# E-Card.net
KiCad netlist of a schematic drawn in Altium Designer
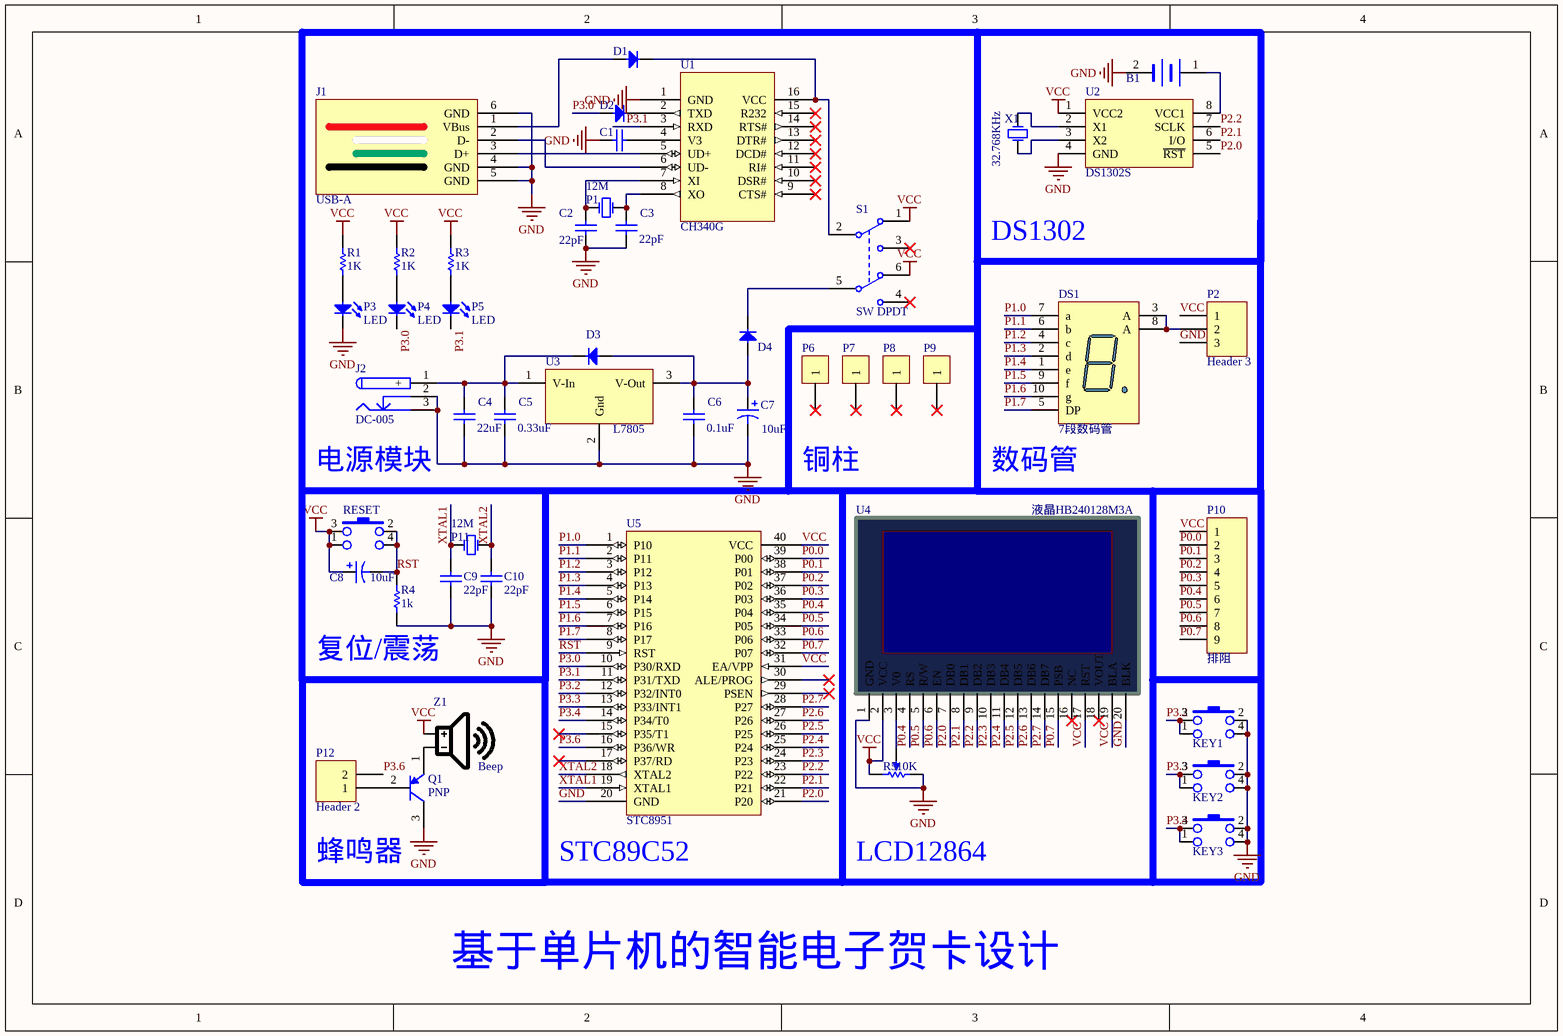
[diagram p0: E-Card.SchDoc]

(export (version "E")
  (design (tool "Eeschema 10.0.6"))
  (components
    (comp (ref "B1") (value "CR1220") (footprint "BATTERY") (libsource (lib "E-Card") (part "BATTERY")))
    (comp (ref "C1")
      (value "0.1uF")
      (footprint "Cap")
      (description "普通电容")
      (libsource (lib "E-Card") (part "Cap"))
    )
    (comp (ref "C2")
      (value "22pF")
      (footprint "Cap")
      (description "普通电容")
      (libsource (lib "E-Card") (part "Cap"))
    )
    (comp (ref "C3")
      (value "22pF")
      (footprint "Cap")
      (description "普通电容")
      (libsource (lib "E-Card") (part "Cap"))
    )
    (comp (ref "C4")
      (value "22uF")
      (footprint "Cap")
      (description "普通电容")
      (libsource (lib "E-Card") (part "Cap"))
    )
    (comp (ref "C5")
      (value "0.33uF")
      (footprint "Cap")
      (description "普通电容")
      (libsource (lib "E-Card") (part "Cap"))
    )
    (comp (ref "C6")
      (value "0.1uF")
      (footprint "Cap")
      (description "普通电容")
      (libsource (lib "E-Card") (part "Cap"))
    )
    (comp (ref "C7")
      (value "10uF")
      (footprint "电解电容")
      (description "电解电容")
      (libsource (lib "E-Card") (part "电解电容"))
    )
    (comp (ref "C8")
      (value "10uF")
      (footprint "电解电容")
      (description "电解电容")
      (libsource (lib "E-Card") (part "电解电容"))
    )
    (comp (ref "C9")
      (value "22pF")
      (footprint "Cap")
      (description "普通电容")
      (libsource (lib "E-Card") (part "Cap"))
    )
    (comp (ref "C10")
      (value "22pF")
      (footprint "Cap")
      (description "普通电容")
      (libsource (lib "E-Card") (part "Cap"))
    )
    (comp (ref "D1")
      (value "Diode")
      (footprint "Diode")
      (description "二极管")
      (fields (field (name "PUBLISHER") "Altium Limited"))
      (libsource (lib "E-Card") (part "Diode"))
    )
    (comp (ref "D2")
      (value "1N4007")
      (footprint "Diode")
      (description "二极管Diode")
      (fields (field (name "PUBLISHER") "Altium Limited"))
      (libsource (lib "E-Card") (part "Diode"))
    )
    (comp (ref "D3")
      (value "Diode")
      (footprint "Diode")
      (description "二极管")
      (fields (field (name "PUBLISHER") "Altium Limited"))
      (libsource (lib "E-Card") (part "Diode"))
    )
    (comp (ref "D4")
      (value "Diode")
      (footprint "Diode")
      (description "二极管")
      (fields (field (name "PUBLISHER") "Altium Limited"))
      (libsource (lib "E-Card") (part "Diode"))
    )
    (comp (ref "DS1")
      (value "7-Segment")
      (footprint "7-Segment")
      (description "14.2 mm General Purpose Blue 7-Segment Display: CA, RH DP, Gray Surface")
      (fields (field (name "ALTIUM_UNNAMED_1") "7段数码管") (field (name "PUBLISHER") "Altium Limited"))
      (libsource (lib "E-Card") (part "7-Segment"))
    )
    (comp (ref "J1") (value "USB-A") (footprint "USB-A") (libsource (lib "E-Card") (part "USB-A")))
    (comp (ref "J2")
      (value "DC-005")
      (footprint "DC JACK")
      (description "DC 电源座")
      (fields (field (name "MANUFACTURER") "Kycon"))
      (libsource (lib "E-Card") (part "DC JACK"))
    )
    (comp (ref "KEY1") (value "SW-66B7") (footprint "SW-66") (libsource (lib "E-Card") (part "SW-66B7")))
    (comp (ref "KEY2") (value "SW-66B7") (footprint "SW-66") (libsource (lib "E-Card") (part "SW-66B7")))
    (comp (ref "KEY3") (value "SW-66B7") (footprint "SW-66") (libsource (lib "E-Card") (part "SW-66B7")))
    (comp (ref "P1")
      (value "12M")
      (footprint "XTAL 12M")
      (description "12MHZ振荡器 【2PIN】")
      (libsource (lib "E-Card") (part "XTAL 12M"))
    )
    (comp (ref "P2")
      (value "Header 3")
      (footprint "Header 3")
      (description "Header, 3-Pin")
      (fields (field (name "PUBLISHER") "Altium Limited"))
      (libsource (lib "E-Card") (part "Header 3"))
    )
    (comp (ref "P3")
      (value "LED")
      (footprint "LED")
      (description "LED灯")
      (libsource (lib "E-Card") (part "LED"))
    )
    (comp (ref "P4")
      (value "LED")
      (footprint "LED")
      (description "LED灯")
      (libsource (lib "E-Card") (part "LED"))
    )
    (comp (ref "P5")
      (value "LED")
      (footprint "LED")
      (description "LED灯")
      (libsource (lib "E-Card") (part "LED"))
    )
    (comp (ref "P6")
      (value "CU-M3X6-10")
      (footprint "CU-M3X6-10")
      (description "10mm长M3六角铜柱")
      (fields (field (name "PUBLISHER") "Altium Limited"))
      (libsource (lib "E-Card") (part "CU-M3X6-10"))
    )
    (comp (ref "P7")
      (value "CU-M3X6-10")
      (footprint "CU-M3X6-10")
      (description "10mm长M3六角铜柱")
      (fields (field (name "PUBLISHER") "Altium Limited"))
      (libsource (lib "E-Card") (part "CU-M3X6-10"))
    )
    (comp (ref "P8")
      (value "CU-M3X6-10")
      (footprint "CU-M3X6-10")
      (description "10mm长M3六角铜柱")
      (fields (field (name "PUBLISHER") "Altium Limited"))
      (libsource (lib "E-Card") (part "CU-M3X6-10"))
    )
    (comp (ref "P9")
      (value "CU-M3X6-10")
      (footprint "CU-M3X6-10")
      (description "10mm长M3六角铜柱")
      (fields (field (name "PUBLISHER") "Altium Limited"))
      (libsource (lib "E-Card") (part "CU-M3X6-10"))
    )
    (comp (ref "P10")
      (value "排阻")
      (footprint "排阻")
      (description "Header, 9-Pin")
      (fields (field (name "PUBLISHER") "Altium Limited"))
      (libsource (lib "E-Card") (part "排阻"))
    )
    (comp (ref "P11")
      (value "12M")
      (footprint "XTAL 12M")
      (description "12MHZ振荡器 【2PIN】")
      (libsource (lib "E-Card") (part "XTAL 12M"))
    )
    (comp (ref "P12")
      (value "Header 2")
      (footprint "Header 2")
      (description "针座/孔座 180度")
      (fields (field (name "PUBLISHER") "Altium Limited"))
      (libsource (lib "E-Card") (part "Header 2"))
    )
    (comp (ref "Q1")
      (value "PNP")
      (footprint "PNP")
      (description "PNP Bipolar Transistor")
      (fields (field (name "PUBLISHER") "Altium Limited"))
      (libsource (lib "E-Card") (part "PNP"))
    )
    (comp (ref "R1")
      (value "1K")
      (footprint "RES")
      (description "电阻")
      (libsource (lib "E-Card") (part "RES"))
    )
    (comp (ref "R2")
      (value "1K")
      (footprint "RES")
      (description "电阻")
      (libsource (lib "E-Card") (part "RES"))
    )
    (comp (ref "R3")
      (value "1K")
      (footprint "RES")
      (description "电阻")
      (libsource (lib "E-Card") (part "RES"))
    )
    (comp (ref "R4")
      (value "1k")
      (footprint "RES")
      (description "电阻")
      (libsource (lib "E-Card") (part "RES"))
    )
    (comp (ref "R5")
      (value "10K")
      (footprint "RPot")
      (description "可调 电阻")
      (fields (field (name "Comment") "RPot") (field (name "PUBLISHER") "Altium Limited"))
      (libsource (lib "E-Card") (part "RPot"))
    )
    (comp (ref "RESET") (value "SW-66B7") (footprint "SW-66") (libsource (lib "E-Card") (part "SW-66B7")))
    (comp (ref "S1")
      (value "SW DPDT")
      (footprint "SW DPDT")
      (description "自锁开关 （双刀双掷）")
      (fields (field (name "PUBLISHER") "Altium Limited"))
      (libsource (lib "E-Card") (part "SW DPDT"))
    )
    (comp (ref "U1")
      (value "CH340G")
      (footprint "CH340G")
      (description "USB to TTL Serial / UART")
      (libsource (lib "E-Card") (part "CH340G"))
    )
    (comp (ref "U2")
      (value "DS1302S")
      (footprint "DS1302")
      (description "时钟芯片 SOP127P780-8")
      (libsource (lib "E-Card") (part "DS1302"))
    )
    (comp (ref "U3")
      (value "L7805")
      (footprint "L7805")
      (description "1.5A Vin:40V(max) Vout:5-24V -55 ~ 150°C LDO稳压器")
      (libsource (lib "E-Card") (part "L7805"))
    )
    (comp (ref "U4")
      (value "液晶HB240128M3A")
      (footprint "LCD12864")
      (libsource (lib "E-Card") (part "液晶HB240128M3A"))
    )
    (comp (ref "U5")
      (value "STC8951")
      (footprint "STC8951")
      (description "51单片机")
      (libsource (lib "E-Card") (part "STC8951"))
    )
    (comp (ref "X1")
      (value "32.768KHz")
      (footprint "XTAL 32768")
      (description "32768HZ振荡器 【2PIN】")
      (libsource (lib "E-Card") (part "XTAL 32768"))
    )
    (comp (ref "Z1")
      (value "Beep")
      (footprint "Beep")
      (description "蜂鸣器")
      (libsource (lib "E-Card") (part "Beep"))
    )
  )
  (nets
    (net (code "1") (name "/P0.0") (class "Default")
      (node (ref "P10") (pin "2") (pinfunction "2_2") (pintype "passive"))
      (node (ref "U5") (pin "39") (pinfunction "P00_39") (pintype "bidirectional"))
    )
    (net (code "2") (name "/P0.1") (class "Default")
      (node (ref "P10") (pin "3") (pinfunction "3_3") (pintype "passive"))
      (node (ref "U5") (pin "38") (pinfunction "P01_38") (pintype "bidirectional"))
    )
    (net (code "3") (name "/P0.2") (class "Default")
      (node (ref "P10") (pin "4") (pinfunction "4_4") (pintype "passive"))
      (node (ref "U5") (pin "37") (pinfunction "P02_37") (pintype "bidirectional"))
    )
    (net (code "4") (name "/P0.3") (class "Default")
      (node (ref "P10") (pin "5") (pinfunction "5_5") (pintype "passive"))
      (node (ref "U5") (pin "36") (pinfunction "P03_36") (pintype "bidirectional"))
    )
    (net (code "5") (name "/P0.4") (class "Default")
      (node (ref "P10") (pin "6") (pinfunction "6_6") (pintype "passive"))
      (node (ref "U4") (pin "4") (pinfunction "RS_4") (pintype "passive"))
      (node (ref "U5") (pin "35") (pinfunction "P04_35") (pintype "bidirectional"))
    )
    (net (code "6") (name "/P0.5") (class "Default")
      (node (ref "P10") (pin "7") (pinfunction "7_7") (pintype "passive"))
      (node (ref "U4") (pin "5") (pinfunction "R/W_5") (pintype "passive"))
      (node (ref "U5") (pin "34") (pinfunction "P05_34") (pintype "bidirectional"))
    )
    (net (code "7") (name "/P0.6") (class "Default")
      (node (ref "P10") (pin "8") (pinfunction "8_8") (pintype "passive"))
      (node (ref "U4") (pin "6") (pinfunction "EN_6") (pintype "passive"))
      (node (ref "U5") (pin "33") (pinfunction "P06_33") (pintype "bidirectional"))
    )
    (net (code "8") (name "/P0.7") (class "Default")
      (node (ref "P10") (pin "9") (pinfunction "9_9") (pintype "passive"))
      (node (ref "U4") (pin "15") (pinfunction "PSB_15") (pintype "passive"))
      (node (ref "U5") (pin "32") (pinfunction "P07_32") (pintype "bidirectional"))
    )
    (net (code "9") (name "/P1.0") (class "Default")
      (node (ref "DS1") (pin "7") (pinfunction "a_7") (pintype "passive"))
      (node (ref "U5") (pin "1") (pinfunction "P10_1") (pintype "bidirectional"))
    )
    (net (code "10") (name "/P1.1") (class "Default")
      (node (ref "DS1") (pin "6") (pinfunction "b_6") (pintype "passive"))
      (node (ref "U5") (pin "2") (pinfunction "P11_2") (pintype "bidirectional"))
    )
    (net (code "11") (name "/P1.2") (class "Default")
      (node (ref "DS1") (pin "4") (pinfunction "c_4") (pintype "passive"))
      (node (ref "U5") (pin "3") (pinfunction "P12_3") (pintype "bidirectional"))
    )
    (net (code "12") (name "/P1.3") (class "Default")
      (node (ref "DS1") (pin "2") (pinfunction "d_2") (pintype "passive"))
      (node (ref "U5") (pin "4") (pinfunction "P13_4") (pintype "bidirectional"))
    )
    (net (code "13") (name "/P1.4") (class "Default")
      (node (ref "DS1") (pin "1") (pinfunction "e_1") (pintype "passive"))
      (node (ref "U5") (pin "5") (pinfunction "P14_5") (pintype "bidirectional"))
    )
    (net (code "14") (name "/P1.5") (class "Default")
      (node (ref "DS1") (pin "9") (pinfunction "f_9") (pintype "passive"))
      (node (ref "U5") (pin "6") (pinfunction "P15_6") (pintype "bidirectional"))
    )
    (net (code "15") (name "/P1.6") (class "Default")
      (node (ref "DS1") (pin "10") (pinfunction "g_10") (pintype "passive"))
      (node (ref "U5") (pin "7") (pinfunction "P16_7") (pintype "bidirectional"))
    )
    (net (code "16") (name "/P1.7") (class "Default")
      (node (ref "DS1") (pin "5") (pinfunction "DP_5") (pintype "passive"))
      (node (ref "U5") (pin "8") (pinfunction "P17_8") (pintype "bidirectional"))
    )
    (net (code "17") (name "/P2.0") (class "Default")
      (node (ref "U2") (pin "5") (pinfunction "~{RST}_5") (pintype "passive"))
      (node (ref "U4") (pin "7") (pinfunction "DB0_7") (pintype "passive"))
      (node (ref "U5") (pin "21") (pinfunction "P20_21") (pintype "bidirectional"))
    )
    (net (code "18") (name "/P2.1") (class "Default")
      (node (ref "U2") (pin "6") (pinfunction "I/O_6") (pintype "passive"))
      (node (ref "U4") (pin "8") (pinfunction "DB1_8") (pintype "passive"))
      (node (ref "U5") (pin "22") (pinfunction "P21_22") (pintype "bidirectional"))
    )
    (net (code "19") (name "/P2.2") (class "Default")
      (node (ref "U2") (pin "7") (pinfunction "SCLK_7") (pintype "passive"))
      (node (ref "U4") (pin "9") (pinfunction "DB2_9") (pintype "passive"))
      (node (ref "U5") (pin "23") (pinfunction "P22_23") (pintype "bidirectional"))
    )
    (net (code "20") (name "/P2.3") (class "Default")
      (node (ref "U4") (pin "10") (pinfunction "DB3_10") (pintype "passive"))
      (node (ref "U5") (pin "24") (pinfunction "P23_24") (pintype "bidirectional"))
    )
    (net (code "21") (name "/P2.4") (class "Default")
      (node (ref "U4") (pin "11") (pinfunction "DB4_11") (pintype "passive"))
      (node (ref "U5") (pin "25") (pinfunction "P24_25") (pintype "bidirectional"))
    )
    (net (code "22") (name "/P2.5") (class "Default")
      (node (ref "U4") (pin "12") (pinfunction "DB5_12") (pintype "passive"))
      (node (ref "U5") (pin "26") (pinfunction "P25_26") (pintype "bidirectional"))
    )
    (net (code "23") (name "/P2.6") (class "Default")
      (node (ref "U4") (pin "13") (pinfunction "DB6_13") (pintype "passive"))
      (node (ref "U5") (pin "27") (pinfunction "P26_27") (pintype "bidirectional"))
    )
    (net (code "24") (name "/P2.7") (class "Default")
      (node (ref "U4") (pin "14") (pinfunction "DB7_14") (pintype "passive"))
      (node (ref "U5") (pin "28") (pinfunction "P27_28") (pintype "bidirectional"))
    )
    (net (code "25") (name "/P3.0") (class "Default")
      (node (ref "D2") (pin "1") (pinfunction "A_1") (pintype "passive"))
      (node (ref "P4") (pin "2") (pinfunction "K_2") (pintype "passive"))
      (node (ref "U5") (pin "10") (pinfunction "P30/RXD_10") (pintype "bidirectional"))
    )
    (net (code "26") (name "/P3.1") (class "Default")
      (node (ref "P5") (pin "2") (pinfunction "K_2") (pintype "passive"))
      (node (ref "U1") (pin "3") (pinfunction "RXD_3") (pintype "input"))
      (node (ref "U5") (pin "11") (pinfunction "P31/TXD_11") (pintype "bidirectional"))
    )
    (net (code "27") (name "/P3.2") (class "Default")
      (node (ref "KEY1") (pin "1") (pinfunction "1_1") (pintype "passive"))
      (node (ref "KEY1") (pin "3") (pinfunction "3_3") (pintype "passive"))
      (node (ref "U5") (pin "12") (pinfunction "P32/INT0_12") (pintype "bidirectional"))
    )
    (net (code "28") (name "/P3.3") (class "Default")
      (node (ref "KEY2") (pin "1") (pinfunction "1_1") (pintype "passive"))
      (node (ref "KEY2") (pin "3") (pinfunction "3_3") (pintype "passive"))
      (node (ref "U5") (pin "13") (pinfunction "P33/INT1_13") (pintype "bidirectional"))
    )
    (net (code "29") (name "/P3.4") (class "Default")
      (node (ref "KEY3") (pin "1") (pinfunction "1_1") (pintype "passive"))
      (node (ref "KEY3") (pin "3") (pinfunction "3_3") (pintype "passive"))
      (node (ref "U5") (pin "14") (pinfunction "P34/T0_14") (pintype "bidirectional"))
    )
    (net (code "30") (name "/P3.6") (class "Default")
      (node (ref "P12") (pin "2") (pinfunction "2_2") (pintype "passive"))
      (node (ref "U5") (pin "16") (pinfunction "P36/WR_16") (pintype "bidirectional"))
    )
    (net (code "31") (name "/RST") (class "Default")
      (node (ref "C8") (pin "2") (pinfunction "2_2") (pintype "passive"))
      (node (ref "R4") (pin "2") (pinfunction "2_2") (pintype "passive"))
      (node (ref "RESET") (pin "2") (pinfunction "2_2") (pintype "passive"))
      (node (ref "RESET") (pin "4") (pinfunction "4_4") (pintype "passive"))
      (node (ref "U5") (pin "9") (pinfunction "RST_9") (pintype "input"))
    )
    (net (code "32") (name "/XTAL1") (class "Default")
      (node (ref "C9") (pin "2") (pinfunction "2_2") (pintype "passive"))
      (node (ref "P11") (pin "1") (pinfunction "OSC1_1") (pintype "passive"))
      (node (ref "U5") (pin "19") (pinfunction "XTAL1_19") (pintype "input"))
    )
    (net (code "33") (name "/XTAL2") (class "Default")
      (node (ref "C10") (pin "2") (pinfunction "2_2") (pintype "passive"))
      (node (ref "P11") (pin "2") (pinfunction "OSC2_2") (pintype "passive"))
      (node (ref "U5") (pin "18") (pinfunction "XTAL2_18") (pintype "output"))
    )
    (net (code "34") (name "GND") (class "Default")
      (node (ref "B1") (pin "2") (pinfunction "-_2") (pintype "passive"))
      (node (ref "C1") (pin "1") (pinfunction "1_1") (pintype "passive"))
      (node (ref "C10") (pin "1") (pinfunction "1_1") (pintype "passive"))
      (node (ref "C2") (pin "2") (pinfunction "2_2") (pintype "passive"))
      (node (ref "C3") (pin "2") (pinfunction "2_2") (pintype "passive"))
      (node (ref "C4") (pin "2") (pinfunction "2_2") (pintype "passive"))
      (node (ref "C5") (pin "2") (pinfunction "2_2") (pintype "passive"))
      (node (ref "C6") (pin "1") (pinfunction "1_1") (pintype "passive"))
      (node (ref "C7") (pin "2") (pinfunction "2_2") (pintype "passive"))
      (node (ref "C9") (pin "1") (pinfunction "1_1") (pintype "passive"))
      (node (ref "J1") (pin "4") (pinfunction "GND_4") (pintype "passive"))
      (node (ref "J1") (pin "5") (pinfunction "GND_5") (pintype "passive"))
      (node (ref "J1") (pin "6") (pinfunction "GND_6") (pintype "passive"))
      (node (ref "J2") (pin "2") (pintype "power_in"))
      (node (ref "J2") (pin "3") (pinfunction "-_3") (pintype "power_in"))
      (node (ref "KEY1") (pin "2") (pinfunction "2_2") (pintype "passive"))
      (node (ref "KEY1") (pin "4") (pinfunction "4_4") (pintype "passive"))
      (node (ref "KEY2") (pin "2") (pinfunction "2_2") (pintype "passive"))
      (node (ref "KEY2") (pin "4") (pinfunction "4_4") (pintype "passive"))
      (node (ref "KEY3") (pin "2") (pinfunction "2_2") (pintype "passive"))
      (node (ref "KEY3") (pin "4") (pinfunction "4_4") (pintype "passive"))
      (node (ref "P2") (pin "3") (pinfunction "3_3") (pintype "passive"))
      (node (ref "P3") (pin "2") (pinfunction "K_2") (pintype "passive"))
      (node (ref "Q1") (pin "3") (pinfunction "C_3") (pintype "passive"))
      (node (ref "R4") (pin "1") (pinfunction "1_1") (pintype "passive"))
      (node (ref "R5") (pin "2") (pinfunction "TOP_2") (pintype "passive"))
      (node (ref "U1") (pin "1") (pinfunction "GND_1") (pintype "power_in"))
      (node (ref "U2") (pin "4") (pinfunction "GND_4") (pintype "passive"))
      (node (ref "U3") (pin "2") (pinfunction "Gnd_2") (pintype "passive"))
      (node (ref "U4") (pin "1") (pinfunction "GND_1") (pintype "passive"))
      (node (ref "U4") (pin "20") (pinfunction "BLK_20") (pintype "passive"))
      (node (ref "U5") (pin "20") (pinfunction "GND_20") (pintype "power_in"))
    )
    (net (code "35") (name "Net-(B1-+)") (class "Default")
      (node (ref "B1") (pin "1") (pinfunction "+_1") (pintype "passive"))
      (node (ref "U2") (pin "8") (pinfunction "VCC1_8") (pintype "passive"))
    )
    (net (code "36") (name "Net-(D1-A)") (class "Default")
      (node (ref "D1") (pin "1") (pinfunction "A_1") (pintype "passive"))
      (node (ref "J1") (pin "1") (pinfunction "VBus_1") (pintype "passive"))
    )
    (net (code "37") (name "Net-(D1-K)") (class "Default")
      (node (ref "D1") (pin "2") (pinfunction "K_2") (pintype "passive"))
      (node (ref "S1") (pin "2") (pinfunction "COMMON1_2") (pintype "passive"))
      (node (ref "U1") (pin "16") (pinfunction "VCC_16") (pintype "power_in"))
    )
    (net (code "38") (name "Net-(D2-K)") (class "Default")
      (node (ref "D2") (pin "2") (pinfunction "K_2") (pintype "passive"))
      (node (ref "U1") (pin "2") (pinfunction "TXD_2") (pintype "output"))
    )
    (net (code "39") (name "Net-(D3-A)") (class "Default")
      (node (ref "C6") (pin "2") (pinfunction "2_2") (pintype "passive"))
      (node (ref "C7") (pin "1") (pinfunction "1_1") (pintype "passive"))
      (node (ref "D3") (pin "1") (pinfunction "A_1") (pintype "passive"))
      (node (ref "D4") (pin "1") (pinfunction "A_1") (pintype "passive"))
      (node (ref "U3") (pin "3") (pinfunction "V-Out_3") (pintype "passive"))
    )
    (net (code "40") (name "Net-(D3-K)") (class "Default")
      (node (ref "C4") (pin "1") (pinfunction "1_1") (pintype "passive"))
      (node (ref "C5") (pin "1") (pinfunction "1_1") (pintype "passive"))
      (node (ref "D3") (pin "2") (pinfunction "K_2") (pintype "passive"))
      (node (ref "J2") (pin "1") (pinfunction "+_1") (pintype "power_in"))
      (node (ref "U3") (pin "1") (pinfunction "V-In_1") (pintype "passive"))
    )
    (net (code "41") (name "Net-(D4-K)") (class "Default")
      (node (ref "D4") (pin "2") (pinfunction "K_2") (pintype "passive"))
      (node (ref "S1") (pin "5") (pinfunction "COMMON2_5") (pintype "passive"))
    )
    (net (code "42") (name "Net-(DS1-A-Pad3)") (class "Default")
      (node (ref "DS1") (pin "3") (pinfunction "A_3") (pintype "passive"))
      (node (ref "DS1") (pin "8") (pinfunction "A_8") (pintype "passive"))
      (node (ref "P2") (pin "2") (pinfunction "2_2") (pintype "passive"))
    )
    (net (code "43") (name "Net-(J1-D+)") (class "Default")
      (node (ref "J1") (pin "3") (pinfunction "D+_3") (pintype "passive"))
      (node (ref "U1") (pin "5") (pinfunction "UD+_5") (pintype "bidirectional"))
    )
    (net (code "44") (name "Net-(J1-D-)") (class "Default")
      (node (ref "J1") (pin "2") (pinfunction "D-_2") (pintype "passive"))
      (node (ref "U1") (pin "6") (pinfunction "UD-_6") (pintype "bidirectional"))
    )
    (net (code "45") (name "Net-(P1-OSC1)") (class "Default")
      (node (ref "C2") (pin "1") (pinfunction "1_1") (pintype "passive"))
      (node (ref "P1") (pin "1") (pinfunction "OSC1_1") (pintype "passive"))
      (node (ref "U1") (pin "7") (pinfunction "XI_7") (pintype "input"))
    )
    (net (code "46") (name "Net-(P1-OSC2)") (class "Default")
      (node (ref "C3") (pin "1") (pinfunction "1_1") (pintype "passive"))
      (node (ref "P1") (pin "2") (pinfunction "OSC2_2") (pintype "passive"))
      (node (ref "U1") (pin "8") (pinfunction "XO_8") (pintype "output"))
    )
    (net (code "47") (name "Net-(P3-A)") (class "Default")
      (node (ref "P3") (pin "1") (pinfunction "A_1") (pintype "passive"))
      (node (ref "R1") (pin "1") (pinfunction "1_1") (pintype "passive"))
    )
    (net (code "48") (name "Net-(P4-A)") (class "Default")
      (node (ref "P4") (pin "1") (pinfunction "A_1") (pintype "passive"))
      (node (ref "R2") (pin "1") (pinfunction "1_1") (pintype "passive"))
    )
    (net (code "49") (name "Net-(P5-A)") (class "Default")
      (node (ref "P5") (pin "1") (pinfunction "A_1") (pintype "passive"))
      (node (ref "R3") (pin "1") (pinfunction "1_1") (pintype "passive"))
    )
    (net (code "50") (name "Net-(Q1-B)") (class "Default")
      (node (ref "P12") (pin "1") (pinfunction "1_1") (pintype "passive"))
      (node (ref "Q1") (pin "2") (pinfunction "B_2") (pintype "passive"))
    )
    (net (code "51") (name "Net-(Q1-E)") (class "Default")
      (node (ref "Q1") (pin "1") (pinfunction "E_1") (pintype "passive"))
      (node (ref "Z1") (pin "2") (pinfunction "2_2") (pintype "passive"))
    )
    (net (code "52") (name "Net-(R5-TAP)") (class "Default")
      (node (ref "R5") (pin "3") (pinfunction "TAP_3") (pintype "passive"))
      (node (ref "U4") (pin "3") (pinfunction "V0_3") (pintype "passive"))
    )
    (net (code "53") (name "Net-(U1-V3)") (class "Default")
      (node (ref "C1") (pin "2") (pinfunction "2_2") (pintype "passive"))
      (node (ref "U1") (pin "4") (pinfunction "V3_4") (pintype "power_in"))
    )
    (net (code "54") (name "Net-(U2-X1)") (class "Default")
      (node (ref "U2") (pin "2") (pinfunction "X1_2") (pintype "passive"))
      (node (ref "X1") (pin "1") (pintype "passive"))
    )
    (net (code "55") (name "Net-(U2-X2)") (class "Default")
      (node (ref "U2") (pin "3") (pinfunction "X2_3") (pintype "passive"))
      (node (ref "X1") (pin "2") (pintype "power_in"))
    )
    (net (code "56") (name "VCC") (class "Default")
      (node (ref "C8") (pin "1") (pinfunction "1_1") (pintype "passive"))
      (node (ref "P10") (pin "1") (pinfunction "1_1") (pintype "passive"))
      (node (ref "P2") (pin "1") (pinfunction "1_1") (pintype "passive"))
      (node (ref "R1") (pin "2") (pinfunction "2_2") (pintype "passive"))
      (node (ref "R2") (pin "2") (pinfunction "2_2") (pintype "passive"))
      (node (ref "R3") (pin "2") (pinfunction "2_2") (pintype "passive"))
      (node (ref "R5") (pin "1") (pinfunction "BOT_1") (pintype "passive"))
      (node (ref "RESET") (pin "1") (pinfunction "1_1") (pintype "passive"))
      (node (ref "RESET") (pin "3") (pinfunction "3_3") (pintype "passive"))
      (node (ref "S1") (pin "1") (pinfunction "NC1_1") (pintype "passive"))
      (node (ref "S1") (pin "6") (pinfunction "NC2_6") (pintype "passive"))
      (node (ref "U2") (pin "1") (pinfunction "VCC2_1") (pintype "passive"))
      (node (ref "U4") (pin "17") (pinfunction "RST_17") (pintype "passive"))
      (node (ref "U4") (pin "19") (pinfunction "BLA_19") (pintype "passive"))
      (node (ref "U4") (pin "2") (pinfunction "VCC_2") (pintype "passive"))
      (node (ref "U5") (pin "31") (pinfunction "EA/VPP_31") (pintype "input"))
      (node (ref "U5") (pin "40") (pinfunction "VCC_40") (pintype "power_in"))
      (node (ref "Z1") (pin "1") (pinfunction "1_1") (pintype "passive"))
    )
    (net (code "57") (name "unconnected-(P6-Pad1)") (class "Default")
      (node (ref "P6") (pin "1") (pinfunction "1_1") (pintype "passive+no_connect"))
    )
    (net (code "58") (name "unconnected-(P7-Pad1)") (class "Default")
      (node (ref "P7") (pin "1") (pinfunction "1_1") (pintype "passive+no_connect"))
    )
    (net (code "59") (name "unconnected-(P8-Pad1)") (class "Default")
      (node (ref "P8") (pin "1") (pinfunction "1_1") (pintype "passive+no_connect"))
    )
    (net (code "60") (name "unconnected-(P9-Pad1)") (class "Default")
      (node (ref "P9") (pin "1") (pinfunction "1_1") (pintype "passive+no_connect"))
    )
    (net (code "61") (name "unconnected-(S1-NO1-Pad3)") (class "Default")
      (node (ref "S1") (pin "3") (pinfunction "NO1_3") (pintype "passive+no_connect"))
    )
    (net (code "62") (name "unconnected-(S1-NO2-Pad4)") (class "Default")
      (node (ref "S1") (pin "4") (pinfunction "NO2_4") (pintype "passive+no_connect"))
    )
    (net (code "63") (name "unconnected-(U1-CTS#-Pad9)") (class "Default")
      (node (ref "U1") (pin "9") (pinfunction "CTS#_9") (pintype "input+no_connect"))
    )
    (net (code "64") (name "unconnected-(U1-DCD#-Pad12)") (class "Default")
      (node (ref "U1") (pin "12") (pinfunction "DCD#_12") (pintype "input+no_connect"))
    )
    (net (code "65") (name "unconnected-(U1-DSR#-Pad10)") (class "Default")
      (node (ref "U1") (pin "10") (pinfunction "DSR#_10") (pintype "input+no_connect"))
    )
    (net (code "66") (name "unconnected-(U1-DTR#-Pad13)") (class "Default")
      (node (ref "U1") (pin "13") (pinfunction "DTR#_13") (pintype "output+no_connect"))
    )
    (net (code "67") (name "unconnected-(U1-R232-Pad15)") (class "Default")
      (node (ref "U1") (pin "15") (pinfunction "R232_15") (pintype "input+no_connect"))
    )
    (net (code "68") (name "unconnected-(U1-RI#-Pad11)") (class "Default")
      (node (ref "U1") (pin "11") (pinfunction "RI#_11") (pintype "input+no_connect"))
    )
    (net (code "69") (name "unconnected-(U1-RTS#-Pad14)") (class "Default")
      (node (ref "U1") (pin "14") (pinfunction "RTS#_14") (pintype "output+no_connect"))
    )
    (net (code "70") (name "unconnected-(U4-NC-Pad16)") (class "Default")
      (node (ref "U4") (pin "16") (pinfunction "NC_16") (pintype "passive+no_connect"))
    )
    (net (code "71") (name "unconnected-(U4-VOUT-Pad18)") (class "Default")
      (node (ref "U4") (pin "18") (pinfunction "VOUT_18") (pintype "passive+no_connect"))
    )
    (net (code "72") (name "unconnected-(U5-ALE{slash}PROG-Pad30)") (class "Default")
      (node (ref "U5") (pin "30") (pinfunction "ALE/PROG_30") (pintype "output+no_connect"))
    )
    (net (code "73") (name "unconnected-(U5-P35{slash}T1-Pad15)") (class "Default")
      (node (ref "U5") (pin "15") (pinfunction "P35/T1_15") (pintype "bidirectional+no_connect"))
    )
    (net (code "74") (name "unconnected-(U5-P37{slash}RD-Pad17)") (class "Default")
      (node (ref "U5") (pin "17") (pinfunction "P37/RD_17") (pintype "bidirectional+no_connect"))
    )
    (net (code "75") (name "unconnected-(U5-PSEN-Pad29)") (class "Default")
      (node (ref "U5") (pin "29") (pinfunction "PSEN_29") (pintype "output+no_connect"))
    )
  )
)
